# bno085.net
KiCad netlist of a schematic drawn in Altium Designer
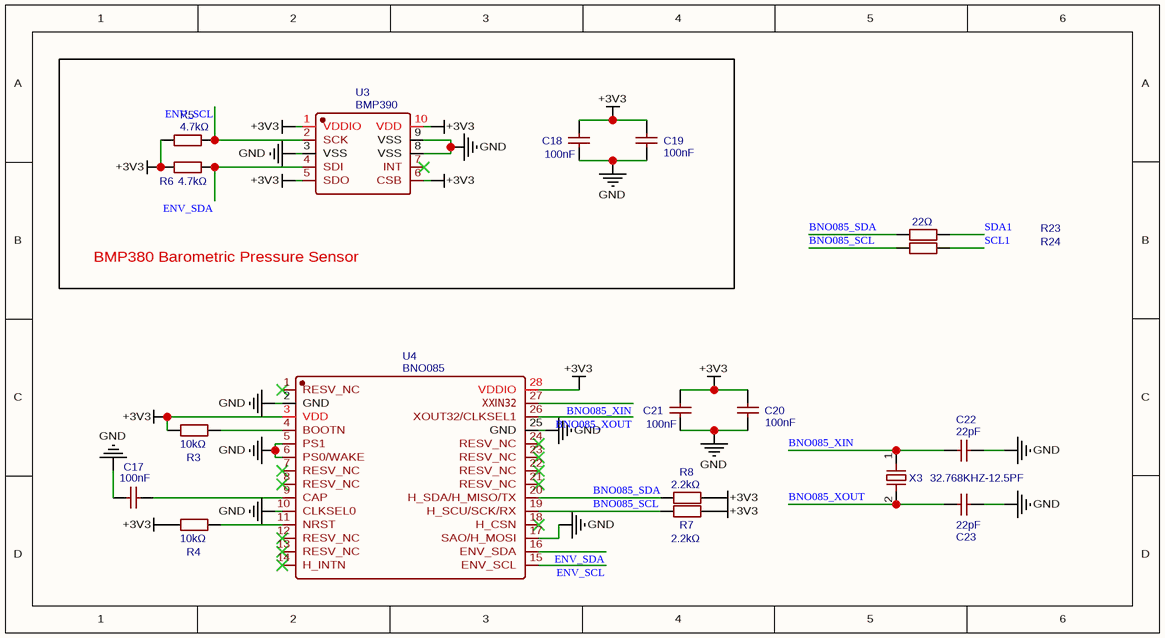
[diagram p0: bno085.schdoc]

(export (version "E")
  (design (tool "Eeschema 10.0.6"))
  (components
    (comp (ref "C17")
      (value "100nF")
      (fields
        (field (name "MANUFACTURER PART") "CL05B104KO5NNNC")
        (field (name "MANUFACTURER") "SAMSUNG(三星)")
      )
      (libsource (lib "altium-import") (part "root_2_100nF_"))
    )
    (comp (ref "C18")
      (value "100nF")
      (fields
        (field (name "MANUFACTURER PART") "CL05B104KO5NNNC")
        (field (name "MANUFACTURER") "SAMSUNG(三星)")
      )
      (libsource (lib "altium-import") (part "root_3_100nF_"))
    )
    (comp (ref "C19")
      (value "100nF")
      (fields
        (field (name "MANUFACTURER PART") "CL05B104KO5NNNC")
        (field (name "MANUFACTURER") "SAMSUNG(三星)")
      )
      (libsource (lib "altium-import") (part "root_3_100nF_"))
    )
    (comp (ref "C20")
      (value "100nF")
      (fields
        (field (name "MANUFACTURER PART") "CL05B104KO5NNNC")
        (field (name "MANUFACTURER") "SAMSUNG(三星)")
      )
      (libsource (lib "altium-import") (part "root_3_100nF_"))
    )
    (comp (ref "C21")
      (value "100nF")
      (fields
        (field (name "MANUFACTURER PART") "CL05B104KO5NNNC")
        (field (name "MANUFACTURER") "SAMSUNG(三星)")
      )
      (libsource (lib "altium-import") (part "root_3_100nF_"))
    )
    (comp (ref "C22")
      (value "22pF")
      (fields (field (name "MANUFACTURER") "FH(风华)") (field (name "MANUFACTURER PART") "0402CG220J500NT"))
      (libsource (lib "altium-import") (part "root_0_22pF_"))
    )
    (comp (ref "C23")
      (value "22pF")
      (fields (field (name "MANUFACTURER") "FH(风华)") (field (name "MANUFACTURER PART") "0402CG220J500NT"))
      (libsource (lib "") (part "root_0_22pF__1"))
    )
    (comp (ref "R3")
      (value "10kΩ")
      (fields
        (field (name "MANUFACTURER") "UNI-ROYAL(厚声)")
        (field (name "MANUFACTURER PART") "0402WGF1002TCE")
      )
      (libsource (lib "altium-import") (part "root_0_10kΩ_"))
    )
    (comp (ref "R4")
      (value "10kΩ")
      (fields
        (field (name "MANUFACTURER") "UNI-ROYAL(厚声)")
        (field (name "MANUFACTURER PART") "0402WGF1002TCE")
      )
      (libsource (lib "altium-import") (part "root_0_10kΩ_"))
    )
    (comp (ref "R5")
      (value "4.7kΩ")
      (fields
        (field (name "MANUFACTURER") "UNI-ROYAL(厚声)")
        (field (name "MANUFACTURER PART") "0402WGF4701TCE")
      )
      (libsource (lib "altium-import") (part "root_0_4.7kΩ_"))
    )
    (comp (ref "R6")
      (value "4.7kΩ")
      (fields
        (field (name "MANUFACTURER") "UNI-ROYAL(厚声)")
        (field (name "MANUFACTURER PART") "0402WGF4701TCE")
      )
      (libsource (lib "altium-import") (part "root_0_4.7kΩ_"))
    )
    (comp (ref "R7")
      (value "2.2kΩ")
      (fields
        (field (name "MANUFACTURER") "UNI-ROYAL(厚声)")
        (field (name "MANUFACTURER PART") "0402WGF2201TCE")
      )
      (libsource (lib "altium-import") (part "root_0_2.2kΩ_"))
    )
    (comp (ref "R8")
      (value "2.2kΩ")
      (fields
        (field (name "MANUFACTURER") "UNI-ROYAL(厚声)")
        (field (name "MANUFACTURER PART") "0402WGF2201TCE")
      )
      (libsource (lib "altium-import") (part "root_0_2.2kΩ_"))
    )
    (comp (ref "R23")
      (value "22Ω")
      (fields
        (field (name "MANUFACTURER") "UNI-ROYAL(厚声)")
        (field (name "MANUFACTURER PART") "0402WGF220JTCE")
      )
      (libsource (lib "altium-import") (part "root_0_22Ω_"))
    )
    (comp (ref "R24")
      (value "22Ω")
      (fields
        (field (name "MANUFACTURER") "UNI-ROYAL(厚声)")
        (field (name "MANUFACTURER PART") "0402WGF220JTCE")
      )
      (libsource (lib "altium-import") (part "root_0_22Ω_"))
    )
    (comp (ref "U3")
      (value "BMP390")
      (fields (field (name "CONTRIBUTOR") "lcsc"))
      (libsource (lib "altium-import") (part "root_0_BMP390_"))
    )
    (comp (ref "U4")
      (value "BNO085")
      (fields (field (name "CONTRIBUTOR") "lcsc"))
      (libsource (lib "altium-import") (part "root_0_BNO085_"))
    )
    (comp (ref "X3")
      (value "32.768KHZ-12.5PF")
      (fields
        (field (name "MANUFACTURER PART") "CMTV-T1A-32.768K-12.5PF-20PPM")
        (field (name "CONTRIBUTOR") "lcsc")
      )
      (libsource (lib "altium-import") (part "root_3_32.768KHZ-12.5PF_"))
    )
  )
  (nets
    (net (code "1") (name "+3V3") (class "Default")
      (node (ref "C18") (pin "2") (pinfunction "2_2") (pintype "passive"))
      (node (ref "C19") (pin "2") (pinfunction "2_2") (pintype "passive"))
      (node (ref "C20") (pin "2") (pinfunction "2_2") (pintype "passive"))
      (node (ref "C21") (pin "2") (pinfunction "2_2") (pintype "passive"))
      (node (ref "R3") (pin "1") (pinfunction "1_1") (pintype "passive"))
      (node (ref "R4") (pin "1") (pinfunction "1_1") (pintype "passive"))
      (node (ref "R5") (pin "1") (pinfunction "1_1") (pintype "passive"))
      (node (ref "R6") (pin "1") (pinfunction "1_1") (pintype "passive"))
      (node (ref "R7") (pin "2") (pinfunction "2_2") (pintype "passive"))
      (node (ref "R8") (pin "2") (pinfunction "2_2") (pintype "passive"))
      (node (ref "U3") (pin "1") (pinfunction "VDDIO_1") (pintype "passive"))
      (node (ref "U3") (pin "10") (pinfunction "VDD_10") (pintype "passive"))
      (node (ref "U3") (pin "5") (pinfunction "SDO_5") (pintype "passive"))
      (node (ref "U3") (pin "6") (pinfunction "CSB_6") (pintype "passive"))
      (node (ref "U4") (pin "28") (pinfunction "VDDIO_28") (pintype "passive"))
      (node (ref "U4") (pin "3") (pinfunction "VDD_3") (pintype "passive"))
    )
    (net (code "2") (name "/BNO085_SCL") (class "Default")
      (node (ref "R24") (pin "1") (pinfunction "1_1") (pintype "passive"))
      (node (ref "R7") (pin "1") (pinfunction "1_1") (pintype "passive"))
      (node (ref "U4") (pin "19") (pinfunction "H_SCU/SCK/RX_19") (pintype "passive"))
    )
    (net (code "3") (name "/BNO085_SDA") (class "Default")
      (node (ref "R23") (pin "1") (pinfunction "1_1") (pintype "passive"))
      (node (ref "R8") (pin "1") (pinfunction "1_1") (pintype "passive"))
      (node (ref "U4") (pin "20") (pinfunction "H_SDA/H_MISO/TX_20") (pintype "passive"))
    )
    (net (code "4") (name "/BNO085_XIN") (class "Default")
      (node (ref "C22") (pin "1") (pinfunction "1_1") (pintype "passive"))
      (node (ref "U4") (pin "27") (pinfunction "XⅪN32_27") (pintype "passive"))
      (node (ref "X3") (pin "1") (pinfunction "1_1") (pintype "passive"))
    )
    (net (code "5") (name "/BNO085_XOUT") (class "Default")
      (node (ref "C23") (pin "1") (pinfunction "1_1") (pintype "passive"))
      (node (ref "U4") (pin "26") (pinfunction "XOUT32/CLKSEL1_26") (pintype "passive"))
      (node (ref "X3") (pin "2") (pinfunction "2_2") (pintype "passive"))
    )
    (net (code "6") (name "/ENV_SCL") (class "Default")
      (node (ref "R5") (pin "2") (pinfunction "2_2") (pintype "passive"))
      (node (ref "U3") (pin "2") (pinfunction "SCK_2") (pintype "passive"))
      (node (ref "U4") (pin "15") (pinfunction "ENV_SCL_15") (pintype "passive"))
    )
    (net (code "7") (name "/ENV_SDA") (class "Default")
      (node (ref "R6") (pin "2") (pinfunction "2_2") (pintype "passive"))
      (node (ref "U3") (pin "4") (pinfunction "SDI_4") (pintype "passive"))
      (node (ref "U4") (pin "16") (pinfunction "ENV_SDA_16") (pintype "passive"))
    )
    (net (code "8") (name "/SCL1") (class "Default")
      (node (ref "R24") (pin "2") (pinfunction "2_2") (pintype "passive"))
    )
    (net (code "9") (name "/SDA1") (class "Default")
      (node (ref "R23") (pin "2") (pinfunction "2_2") (pintype "passive"))
    )
    (net (code "10") (name "GND") (class "Default")
      (node (ref "C17") (pin "1") (pinfunction "1_1") (pintype "passive"))
      (node (ref "C18") (pin "1") (pinfunction "1_1") (pintype "passive"))
      (node (ref "C19") (pin "1") (pinfunction "1_1") (pintype "passive"))
      (node (ref "C20") (pin "1") (pinfunction "1_1") (pintype "passive"))
      (node (ref "C21") (pin "1") (pinfunction "1_1") (pintype "passive"))
      (node (ref "C22") (pin "2") (pinfunction "2_2") (pintype "passive"))
      (node (ref "C23") (pin "2") (pinfunction "2_2") (pintype "passive"))
      (node (ref "U3") (pin "3") (pinfunction "VSS_3") (pintype "passive"))
      (node (ref "U3") (pin "8") (pinfunction "VSS_8") (pintype "passive"))
      (node (ref "U3") (pin "9") (pinfunction "VSS_9") (pintype "passive"))
      (node (ref "U4") (pin "10") (pinfunction "CLKSEL0_10") (pintype "passive"))
      (node (ref "U4") (pin "17") (pinfunction "SAO/H_MOSI_17") (pintype "passive"))
      (node (ref "U4") (pin "2") (pinfunction "GND_2") (pintype "passive"))
      (node (ref "U4") (pin "25") (pinfunction "GND_25") (pintype "passive"))
      (node (ref "U4") (pin "5") (pinfunction "PS1_5") (pintype "passive"))
      (node (ref "U4") (pin "6") (pinfunction "PS0/WAKE_6") (pintype "passive"))
    )
    (net (code "11") (name "Net-(U4-BOOTN)") (class "Default")
      (node (ref "R3") (pin "2") (pinfunction "2_2") (pintype "passive"))
      (node (ref "U4") (pin "4") (pinfunction "BOOTN_4") (pintype "passive"))
    )
    (net (code "12") (name "Net-(U4-CAP)") (class "Default")
      (node (ref "C17") (pin "2") (pinfunction "2_2") (pintype "passive"))
      (node (ref "U4") (pin "9") (pinfunction "CAP_9") (pintype "passive"))
    )
    (net (code "13") (name "Net-(U4-NRST)") (class "Default")
      (node (ref "R4") (pin "2") (pinfunction "2_2") (pintype "passive"))
      (node (ref "U4") (pin "11") (pinfunction "NRST_11") (pintype "passive"))
    )
    (net (code "14") (name "unconnected-(U3-INT-Pad7)") (class "Default")
      (node (ref "U3") (pin "7") (pinfunction "INT_7") (pintype "passive+no_connect"))
    )
    (net (code "15") (name "unconnected-(U4-H_CSN-Pad18)") (class "Default")
      (node (ref "U4") (pin "18") (pinfunction "H_CSN_18") (pintype "passive+no_connect"))
    )
    (net (code "16") (name "unconnected-(U4-H_INTN-Pad14)") (class "Default")
      (node (ref "U4") (pin "14") (pinfunction "H_INTN_14") (pintype "passive+no_connect"))
    )
    (net (code "17") (name "unconnected-(U4-RESV_NC-Pad1)") (class "Default")
      (node (ref "U4") (pin "1") (pinfunction "RESV_NC_1") (pintype "passive+no_connect"))
    )
    (net (code "18") (name "unconnected-(U4-RESV_NC-Pad7)") (class "Default")
      (node (ref "U4") (pin "7") (pinfunction "RESV_NC_7") (pintype "passive+no_connect"))
    )
    (net (code "19") (name "unconnected-(U4-RESV_NC-Pad8)") (class "Default")
      (node (ref "U4") (pin "8") (pinfunction "RESV_NC_8") (pintype "passive+no_connect"))
    )
    (net (code "20") (name "unconnected-(U4-RESV_NC-Pad12)") (class "Default")
      (node (ref "U4") (pin "12") (pinfunction "RESV_NC_12") (pintype "passive+no_connect"))
    )
    (net (code "21") (name "unconnected-(U4-RESV_NC-Pad13)") (class "Default")
      (node (ref "U4") (pin "13") (pinfunction "RESV_NC_13") (pintype "passive+no_connect"))
    )
    (net (code "22") (name "unconnected-(U4-RESV_NC-Pad21)") (class "Default")
      (node (ref "U4") (pin "21") (pinfunction "RESV_NC_21") (pintype "passive+no_connect"))
    )
    (net (code "23") (name "unconnected-(U4-RESV_NC-Pad22)") (class "Default")
      (node (ref "U4") (pin "22") (pinfunction "RESV_NC_22") (pintype "passive+no_connect"))
    )
    (net (code "24") (name "unconnected-(U4-RESV_NC-Pad23)") (class "Default")
      (node (ref "U4") (pin "23") (pinfunction "RESV_NC_23") (pintype "passive+no_connect"))
    )
    (net (code "25") (name "unconnected-(U4-RESV_NC-Pad24)") (class "Default")
      (node (ref "U4") (pin "24") (pinfunction "RESV_NC_24") (pintype "passive+no_connect"))
    )
  )
)
